# yard-ice-toplevel.net
KiCad netlist of a schematic drawn in Altium Designer
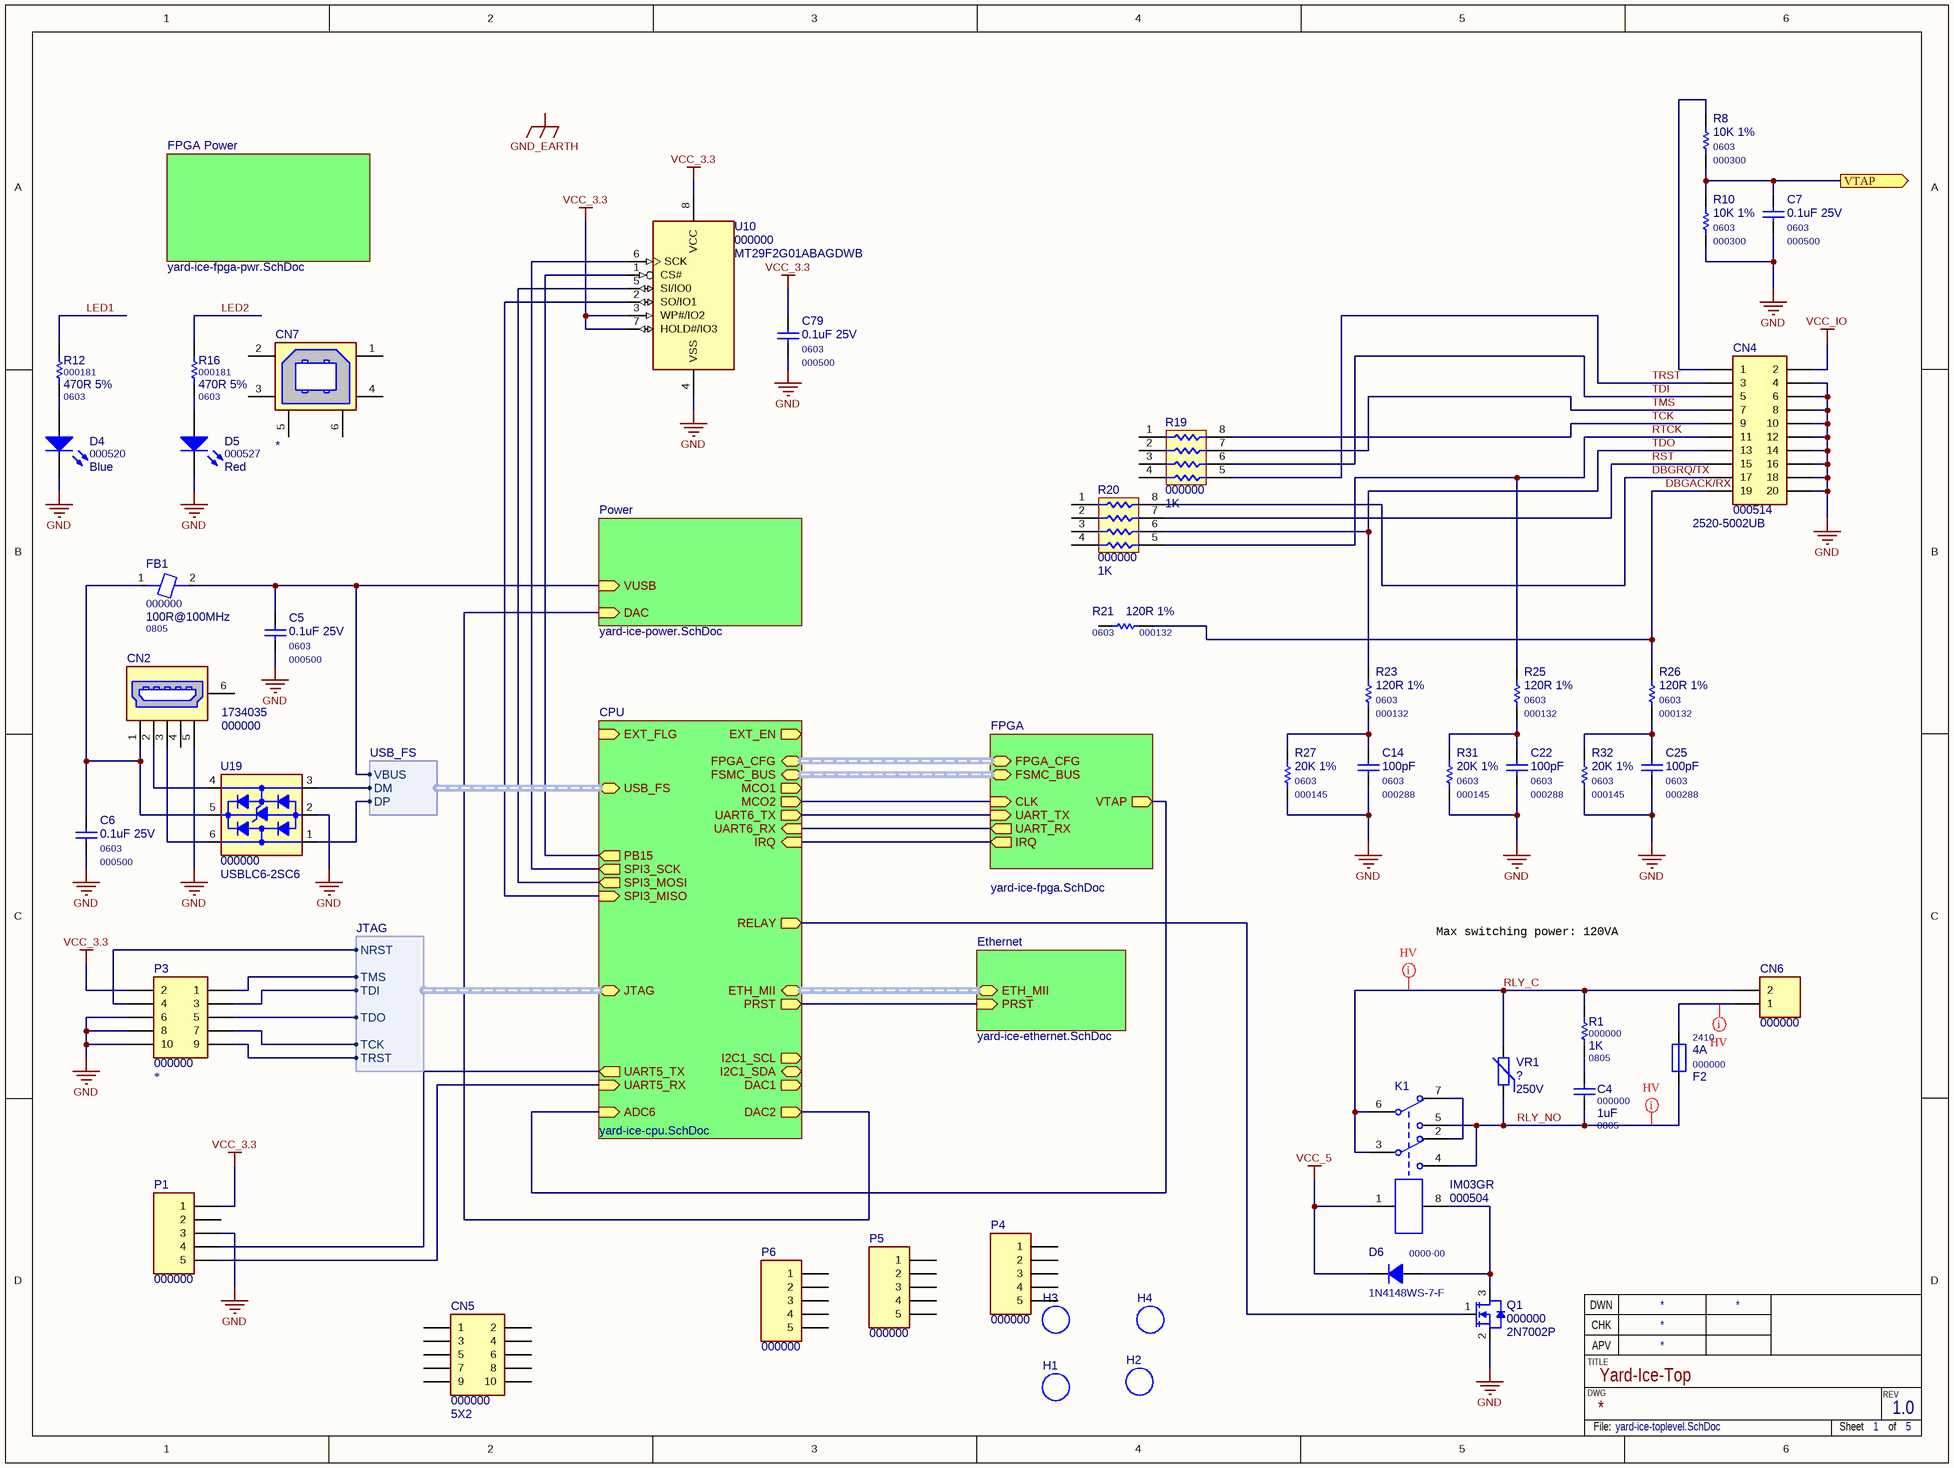
[diagram p0: yard-ice-toplevel.SchDoc]

(export (version "E")
  (design (tool "Eeschema 10.0.6"))
  (components
    (comp (ref "C4")
      (value "000000")
      (footprint "C0805HV")
      (description "SMD Ceramic Chip Capacitor - 0805")
      (fields (field (name "ALTIUM_VALUE") "1uF") (field (name "PACKAGE") "0805"))
      (libsource (lib "discrete-sm") (part "C0805"))
    )
    (comp (ref "C5")
      (value "000500")
      (footprint "C0603M")
      (description "SMD Ceramic Chip Capacitor - 0603 - X7R")
      (fields
        (field (name "ALTIUM_VALUE") "0.1uF 25V")
        (field (name "PACKAGE") "0603")
        (field (name "MF") "TDK")
      )
      (libsource (lib "discrete-sm") (part "C0603"))
    )
    (comp (ref "C6")
      (value "000500")
      (footprint "C0603M")
      (description "SMD Ceramic Chip Capacitor - 0603 - X7R")
      (fields
        (field (name "ALTIUM_VALUE") "0.1uF 25V")
        (field (name "PACKAGE") "0603")
        (field (name "MF") "TDK")
      )
      (libsource (lib "discrete-sm") (part "C0603"))
    )
    (comp (ref "C7")
      (value "000500")
      (footprint "C0603M")
      (description "SMD Ceramic Chip Capacitor - 0603 - X7R")
      (fields
        (field (name "ALTIUM_VALUE") "0.1uF 25V")
        (field (name "PACKAGE") "0603")
        (field (name "MF") "TDK")
      )
      (libsource (lib "discrete-sm") (part "C0603"))
    )
    (comp (ref "C14")
      (value "000288")
      (footprint "C0603M")
      (description "SMD Ceramic Chip Capacitor - 0603")
      (fields (field (name "ALTIUM_VALUE") "100pF") (field (name "PACKAGE") "0603"))
      (libsource (lib "discrete-sm") (part "C0603"))
    )
    (comp (ref "C22")
      (value "000288")
      (footprint "C0603M")
      (description "SMD Ceramic Chip Capacitor - 0603")
      (fields (field (name "ALTIUM_VALUE") "100pF") (field (name "PACKAGE") "0603"))
      (libsource (lib "discrete-sm") (part "C0603"))
    )
    (comp (ref "C25")
      (value "000288")
      (footprint "C0603M")
      (description "SMD Ceramic Chip Capacitor - 0603")
      (fields (field (name "ALTIUM_VALUE") "100pF") (field (name "PACKAGE") "0603"))
      (libsource (lib "discrete-sm") (part "C0603"))
    )
    (comp (ref "C79")
      (value "000500")
      (footprint "C0603M")
      (description "SMD Ceramic Chip Capacitor - 0603 - X7R")
      (fields
        (field (name "ALTIUM_VALUE") "0.1uF 25V")
        (field (name "PACKAGE") "0603")
        (field (name "MF") "TDK")
      )
      (libsource (lib "discrete-sm") (part "C0603"))
    )
    (comp (ref "CN2")
      (value "1734035")
      (footprint "1734035")
      (description "USB Type B Mini - Right Angle - SMD")
      (fields (field (name "MF") "Tyco") (field (name "PN") "000000") (field (name "Comment") "000000"))
      (libsource (lib "tyco-conn") (part "1734035"))
    )
    (comp (ref "CN4")
      (value "000514")
      (footprint "TST-110-04-G-D-RA")
      (description "Shrouded Header, 20 Pos, Right Angle")
      (fields (field (name "ALTIUM_VALUE") "2520-5002UB") (field (name "MF") "3M"))
      (libsource (lib "samtec-board-to-board") (part "Header 10X2"))
    )
    (comp (ref "CN5")
      (value "000000")
      (footprint "TST-105-04-G-D-RA")
      (description "Socket 5-Pin, Dual row")
      (fields (field (name "MF") "Samtec") (field (name "ALTIUM_VALUE") "5X2"))
      (libsource (lib "samtec-board-to-board") (part "Header 5X2"))
    )
    (comp (ref "CN6")
      (value "000000")
      (footprint "691322110002")
      (description "Terminal Block, Header, 2-Pos")
      (libsource (lib "wurth") (part "Term Blk 2"))
    )
    (comp (ref "CN7")
      (value "*")
      (footprint "4-1734376")
      (description "USB Type B - Right Angle - Thru Hole")
      (libsource (lib "tyco-conn") (part "4-1734376"))
    )
    (comp (ref "D4")
      (value "000520")
      (footprint "LED0805L LP")
      (description "LED SMD 0805")
      (fields (field (name "ALTIUM_VALUE") "Blue"))
      (libsource (lib "discrete-sm") (part "LED0805LP"))
    )
    (comp (ref "D5")
      (value "000527")
      (footprint "LED0805L LP")
      (description "LED SMD 0805")
      (fields (field (name "ALTIUM_VALUE") "Red"))
      (libsource (lib "discrete-sm") (part "LED0805LP"))
    )
    (comp (ref "D6")
      (value "0000-00")
      (footprint "SOD-323-M")
      (description "Fast Switching Diode 100V 150mA")
      (fields (field (name "MF") "Diodes Inc") (field (name "MF PN") "1N4148WS-7-F"))
      (libsource (lib "diodes-inc") (part "1N4148WS"))
    )
    (comp (ref "F2")
      (value "000000")
      (footprint "F2410")
      (fields (field (name "PACKAGE") "2410") (field (name "ALTIUM_VALUE") "4A"))
      (libsource (lib "discrete-sm") (part "F2410"))
    )
    (comp (ref "FB1")
      (value "000000")
      (footprint "L0805M")
      (description "SMD Chip Ferrite Bead - 0805")
      (fields (field (name "ALTIUM_VALUE") "100R@100MHz") (field (name "PACKAGE") "0805"))
      (libsource (lib "discrete-sm") (part "FB0805"))
    )
    (comp (ref "H1")
      (value "Hole Non Plated")
      (footprint "Hole NP 3.2x5.0x5.0")
      (libsource (lib "mechanical") (part "Hole Non Plated"))
    )
    (comp (ref "H2")
      (value "Hole Non Plated")
      (footprint "Hole NP 3.2x5.0x5.0")
      (libsource (lib "mechanical") (part "Hole Non Plated"))
    )
    (comp (ref "H3")
      (value "Hole Non Plated")
      (footprint "Hole NP 3.2x5.0x5.0")
      (libsource (lib "mechanical") (part "Hole Non Plated"))
    )
    (comp (ref "H4")
      (value "Hole Non Plated")
      (footprint "Hole NP 3.2x5.0x5.0")
      (libsource (lib "mechanical") (part "Hole Non Plated"))
    )
    (comp (ref "K1")
      (value "000504")
      (footprint "Relay-10X6")
      (description "Dual-Pole Dual-Throw Relay")
      (fields (field (name "ALTIUM_VALUE") "IM03GR") (field (name "MF") "Tyco"))
      (libsource (lib "sm-electromechanical") (part "Relay-DPDT"))
    )
    (comp (ref "P1")
      (value "000000")
      (footprint "TSW-105-07-G-S")
      (description "Header, 5-Pin")
      (libsource (lib "samtec-board-to-board") (part "Header 5"))
    )
    (comp (ref "P3")
      (value "000000")
      (footprint "TSW-105-07-G-D")
      (description "Socket 5-Pin, Dual row")
      (fields (field (name "ALTIUM_VALUE") "*"))
      (libsource (lib "samtec-std-hdr") (part "Header 5X2"))
    )
    (comp (ref "P4")
      (value "000000")
      (footprint "TSW-105-07-G-S")
      (description "Header, 5-Pin")
      (libsource (lib "samtec-board-to-board") (part "Header 5"))
    )
    (comp (ref "P5")
      (value "000000")
      (footprint "TSW-105-07-G-S")
      (description "Header, 5-Pin")
      (libsource (lib "samtec-board-to-board") (part "Header 5"))
    )
    (comp (ref "P6")
      (value "000000")
      (footprint "TSW-105-07-G-S")
      (description "Header, 5-Pin")
      (libsource (lib "samtec-board-to-board") (part "Header 5"))
    )
    (comp (ref "Q1")
      (value "000000")
      (footprint "SOT-23-M")
      (description "N-Channel MOSFET 60V 360mA SOT-23")
      (fields (field (name "ALTIUM_VALUE") "2N7002P"))
      (libsource (lib "nxp") (part "2N7002P"))
    )
    (comp (ref "R1")
      (value "000000")
      (footprint "R0805HV")
      (description "SMD Chip Resistor - 0805")
      (fields (field (name "ALTIUM_VALUE") "1K") (field (name "PACKAGE") "0805"))
      (libsource (lib "discrete-sm") (part "R0805"))
    )
    (comp (ref "R8")
      (value "000300")
      (footprint "R0603M")
      (description "SMD Chip Resistor - 0603")
      (fields (field (name "ALTIUM_VALUE") "10K 1%") (field (name "PACKAGE") "0603"))
      (libsource (lib "discrete-sm") (part "R0603"))
    )
    (comp (ref "R10")
      (value "000300")
      (footprint "R0603M")
      (description "SMD Chip Resistor - 0603")
      (fields (field (name "ALTIUM_VALUE") "10K 1%") (field (name "PACKAGE") "0603"))
      (libsource (lib "discrete-sm") (part "R0603"))
    )
    (comp (ref "R12")
      (value "000181")
      (footprint "R0603M")
      (description "SMD Chip Resistor - 0603")
      (fields (field (name "ALTIUM_VALUE") "470R 5%") (field (name "PACKAGE") "0603"))
      (libsource (lib "discrete-sm") (part "R0603"))
    )
    (comp (ref "R16")
      (value "000181")
      (footprint "R0603M")
      (description "SMD Chip Resistor - 0603")
      (fields (field (name "ALTIUM_VALUE") "470R 5%") (field (name "PACKAGE") "0603"))
      (libsource (lib "discrete-sm") (part "R0603"))
    )
    (comp (ref "R19")
      (value "000000")
      (footprint "R0603x4L")
      (description "SMD Chip Resistor Array - 4x0603")
      (fields (field (name "ALTIUM_VALUE") "1K"))
      (libsource (lib "discrete-sm") (part "R0603x4"))
    )
    (comp (ref "R20")
      (value "000000")
      (footprint "R0603x4L")
      (description "SMD Chip Resistor Array - 4x0603")
      (fields (field (name "ALTIUM_VALUE") "1K"))
      (libsource (lib "discrete-sm") (part "R0603x4"))
    )
    (comp (ref "R21")
      (value "000132")
      (footprint "R0603M")
      (description "SMD Chip Resistor - 0603")
      (fields (field (name "ALTIUM_VALUE") "120R 1%") (field (name "PACKAGE") "0603"))
      (libsource (lib "discrete-sm") (part "R0603"))
    )
    (comp (ref "R23")
      (value "000132")
      (footprint "R0603M")
      (description "SMD Chip Resistor - 0603")
      (fields (field (name "ALTIUM_VALUE") "120R 1%") (field (name "PACKAGE") "0603"))
      (libsource (lib "discrete-sm") (part "R0603"))
    )
    (comp (ref "R25")
      (value "000132")
      (footprint "R0603M")
      (description "SMD Chip Resistor - 0603")
      (fields (field (name "ALTIUM_VALUE") "120R 1%") (field (name "PACKAGE") "0603"))
      (libsource (lib "discrete-sm") (part "R0603"))
    )
    (comp (ref "R26")
      (value "000132")
      (footprint "R0603M")
      (description "SMD Chip Resistor - 0603")
      (fields (field (name "ALTIUM_VALUE") "120R 1%") (field (name "PACKAGE") "0603"))
      (libsource (lib "discrete-sm") (part "R0603"))
    )
    (comp (ref "R27")
      (value "000145")
      (footprint "R0603M")
      (description "SMD Chip Resistor - 0603")
      (fields (field (name "ALTIUM_VALUE") "20K 1%") (field (name "PACKAGE") "0603"))
      (libsource (lib "discrete-sm") (part "R0603"))
    )
    (comp (ref "R31")
      (value "000145")
      (footprint "R0603M")
      (description "SMD Chip Resistor - 0603")
      (fields (field (name "ALTIUM_VALUE") "20K 1%") (field (name "PACKAGE") "0603"))
      (libsource (lib "discrete-sm") (part "R0603"))
    )
    (comp (ref "R32")
      (value "000145")
      (footprint "R0603M")
      (description "SMD Chip Resistor - 0603")
      (fields (field (name "ALTIUM_VALUE") "20K 1%") (field (name "PACKAGE") "0603"))
      (libsource (lib "discrete-sm") (part "R0603"))
    )
    (comp (ref "U10")
      (value "000000")
      (footprint "U-PDFN-8")
      (description "2Gb NANDl Flash Memory,  133MHz, SPI")
      (fields (field (name "MF") "Micron") (field (name "ALTIUM_VALUE") "MT29F2G01ABAGDWB"))
      (libsource (lib "micron") (part "MT29F2G01ABAGDWB"))
    )
    (comp (ref "U19")
      (value "000000")
      (footprint "SOT23-6L")
      (description "USB ESD Protection")
      (fields (field (name "MF") "STMicroelectronics") (field (name "ALTIUM_VALUE") "USBLC6-2SC6"))
      (libsource (lib "st") (part "USBLC6-2SC6"))
    )
    (comp (ref "VR1")
      (value "?")
      (footprint "MOV7x4.8-5.0")
      (description "Varistor (Voltage-Sensitive Resistor)")
      (fields (field (name "ALTIUM_VALUE") "250V"))
      (libsource (lib "discrete-pth") (part "Varistor"))
    )
  )
  (nets
    (net (code "5") (name "/DBGACK{slash}RX") (class "Default")
      (node (ref "CN4") (pin "19") (pinfunction "19_19") (pintype "passive"))
      (node (ref "R21") (pin "1") (pinfunction "1_1") (pintype "passive"))
      (node (ref "R26") (pin "1") (pinfunction "1_1") (pintype "passive"))
    )
    (net (code "6") (name "/DBGRQ{slash}TX") (class "Default")
      (node (ref "CN4") (pin "17") (pinfunction "17_17") (pintype "passive"))
      (node (ref "R20") (pin "8") (pinfunction "8_8") (pintype "passive"))
    )
    (net (code "15") (name "/LED1") (class "Default")
      (node (ref "R12") (pin "1") (pinfunction "1_1") (pintype "passive"))
    )
    (net (code "16") (name "/LED2") (class "Default")
      (node (ref "R16") (pin "1") (pinfunction "1_1") (pintype "passive"))
    )
    (net (code "19") (name "/PB15") (class "Default")
      (node (ref "U10") (pin "1") (pinfunction "CS#_1") (pintype "input"))
    )
    (net (code "21") (name "/RELAY") (class "Default")
      (node (ref "Q1") (pin "1") (pinfunction "G_1") (pintype "passive"))
    )
    (net (code "22") (name "/RLY_C") (class "Default")
      (node (ref "CN6") (pin "2") (pinfunction "2_2") (pintype "passive"))
      (node (ref "K1") (pin "3") (pinfunction "3_3") (pintype "passive"))
      (node (ref "K1") (pin "6") (pinfunction "6_6") (pintype "passive"))
      (node (ref "R1") (pin "2") (pinfunction "2_2") (pintype "passive"))
      (node (ref "VR1") (pin "2") (pinfunction "2_2") (pintype "passive"))
    )
    (net (code "23") (name "/RLY_NO") (class "Default")
      (node (ref "C4") (pin "2") (pinfunction "2_2") (pintype "passive"))
      (node (ref "F2") (pin "1") (pinfunction "1_1") (pintype "passive"))
      (node (ref "K1") (pin "4") (pinfunction "4_4") (pintype "passive"))
      (node (ref "K1") (pin "5") (pinfunction "5_5") (pintype "passive"))
      (node (ref "VR1") (pin "1") (pinfunction "1_1") (pintype "passive"))
    )
    (net (code "24") (name "/RST") (class "Default")
      (node (ref "CN4") (pin "15") (pinfunction "15_15") (pintype "passive"))
      (node (ref "R20") (pin "7") (pinfunction "7_7") (pintype "passive"))
    )
    (net (code "25") (name "/RTCK") (class "Default")
      (node (ref "CN4") (pin "11") (pinfunction "11_11") (pintype "passive"))
      (node (ref "R20") (pin "5") (pinfunction "5_5") (pintype "passive"))
      (node (ref "R25") (pin "1") (pinfunction "1_1") (pintype "passive"))
    )
    (net (code "26") (name "/SPI3_MISO") (class "Default")
      (node (ref "U10") (pin "2") (pinfunction "SO/IO1_2") (pintype "bidirectional"))
    )
    (net (code "27") (name "/SPI3_MOSI") (class "Default")
      (node (ref "U10") (pin "5") (pinfunction "SI/IO0_5") (pintype "bidirectional"))
    )
    (net (code "28") (name "/SPI3_SCK") (class "Default")
      (node (ref "U10") (pin "6") (pinfunction "SCK_6") (pintype "input"))
    )
    (net (code "29") (name "/TCK") (class "Default")
      (node (ref "CN4") (pin "9") (pinfunction "9_9") (pintype "passive"))
      (node (ref "R19") (pin "8") (pinfunction "8_8") (pintype "passive"))
    )
    (net (code "30") (name "/TDI") (class "Default")
      (node (ref "CN4") (pin "5") (pinfunction "5_5") (pintype "passive"))
      (node (ref "R19") (pin "6") (pinfunction "6_6") (pintype "passive"))
    )
    (net (code "31") (name "/TDO") (class "Default")
      (node (ref "CN4") (pin "13") (pinfunction "13_13") (pintype "passive"))
      (node (ref "R20") (pin "6") (pinfunction "6_6") (pintype "passive"))
      (node (ref "R23") (pin "1") (pinfunction "1_1") (pintype "passive"))
    )
    (net (code "32") (name "/TMS") (class "Default")
      (node (ref "CN4") (pin "7") (pinfunction "7_7") (pintype "passive"))
      (node (ref "R19") (pin "7") (pinfunction "7_7") (pintype "passive"))
    )
    (net (code "33") (name "/TRST") (class "Default")
      (node (ref "CN4") (pin "3") (pinfunction "3_3") (pintype "passive"))
      (node (ref "R19") (pin "5") (pinfunction "5_5") (pintype "passive"))
    )
    (net (code "34") (name "/UART5_RX") (class "Default")
      (node (ref "P1") (pin "5") (pinfunction "5_5") (pintype "passive"))
    )
    (net (code "35") (name "/UART5_TX") (class "Default")
      (node (ref "P1") (pin "4") (pinfunction "4_4") (pintype "passive"))
    )
    (net (code "38") (name "/VTAP") (class "Default")
      (node (ref "C7") (pin "1") (pinfunction "1_1") (pintype "passive"))
      (node (ref "R10") (pin "1") (pinfunction "1_1") (pintype "passive"))
      (node (ref "R8") (pin "2") (pinfunction "2_2") (pintype "passive"))
    )
    (net (code "40") (name "/VUSB") (class "Default")
      (node (ref "C5") (pin "1") (pinfunction "1_1") (pintype "passive"))
      (node (ref "FB1") (pin "2") (pinfunction "2_2") (pintype "passive"))
    )
    (net (code "43") (name "GND") (class "Default")
      (node (ref "C14") (pin "2") (pinfunction "2_2") (pintype "passive"))
      (node (ref "C22") (pin "2") (pinfunction "2_2") (pintype "passive"))
      (node (ref "C25") (pin "2") (pinfunction "2_2") (pintype "passive"))
      (node (ref "C5") (pin "2") (pinfunction "2_2") (pintype "passive"))
      (node (ref "C6") (pin "2") (pinfunction "2_2") (pintype "passive"))
      (node (ref "C7") (pin "2") (pinfunction "2_2") (pintype "passive"))
      (node (ref "C79") (pin "2") (pinfunction "2_2") (pintype "passive"))
      (node (ref "CN2") (pin "5") (pinfunction "SHIELD_5") (pintype "passive"))
      (node (ref "CN4") (pin "10") (pinfunction "10_10") (pintype "passive"))
      (node (ref "CN4") (pin "12") (pinfunction "12_12") (pintype "passive"))
      (node (ref "CN4") (pin "14") (pinfunction "14_14") (pintype "passive"))
      (node (ref "CN4") (pin "16") (pinfunction "16_16") (pintype "passive"))
      (node (ref "CN4") (pin "18") (pinfunction "18_18") (pintype "passive"))
      (node (ref "CN4") (pin "20") (pinfunction "20_20") (pintype "passive"))
      (node (ref "CN4") (pin "4") (pinfunction "4_4") (pintype "passive"))
      (node (ref "CN4") (pin "6") (pinfunction "6_6") (pintype "passive"))
      (node (ref "CN4") (pin "8") (pinfunction "8_8") (pintype "passive"))
      (node (ref "D4") (pin "2") (pinfunction "K_2") (pintype "passive"))
      (node (ref "D5") (pin "2") (pinfunction "K_2") (pintype "passive"))
      (node (ref "P1") (pin "3") (pinfunction "3_3") (pintype "passive"))
      (node (ref "P3") (pin "10") (pinfunction "10_10") (pintype "passive"))
      (node (ref "P3") (pin "6") (pinfunction "6_6") (pintype "passive"))
      (node (ref "P3") (pin "8") (pinfunction "8_8") (pintype "passive"))
      (node (ref "Q1") (pin "2") (pinfunction "S_2") (pintype "passive"))
      (node (ref "R10") (pin "2") (pinfunction "2_2") (pintype "passive"))
      (node (ref "R27") (pin "2") (pinfunction "2_2") (pintype "passive"))
      (node (ref "R31") (pin "2") (pinfunction "2_2") (pintype "passive"))
      (node (ref "R32") (pin "2") (pinfunction "2_2") (pintype "passive"))
      (node (ref "U10") (pin "4") (pinfunction "VSS_4") (pintype "power_in"))
      (node (ref "U19") (pin "2") (pinfunction "GND_2") (pintype "power_in"))
    )
    (net (code "45") (name "Net-(C4-Pad1)") (class "Default")
      (node (ref "C4") (pin "1") (pinfunction "1_1") (pintype "passive"))
      (node (ref "R1") (pin "1") (pinfunction "1_1") (pintype "passive"))
    )
    (net (code "46") (name "Net-(C14-Pad1)") (class "Default")
      (node (ref "C14") (pin "1") (pinfunction "1_1") (pintype "passive"))
      (node (ref "R23") (pin "2") (pinfunction "2_2") (pintype "passive"))
      (node (ref "R27") (pin "1") (pinfunction "1_1") (pintype "passive"))
    )
    (net (code "47") (name "Net-(C22-Pad1)") (class "Default")
      (node (ref "C22") (pin "1") (pinfunction "1_1") (pintype "passive"))
      (node (ref "R25") (pin "2") (pinfunction "2_2") (pintype "passive"))
      (node (ref "R31") (pin "1") (pinfunction "1_1") (pintype "passive"))
    )
    (net (code "48") (name "Net-(C25-Pad1)") (class "Default")
      (node (ref "C25") (pin "1") (pinfunction "1_1") (pintype "passive"))
      (node (ref "R26") (pin "2") (pinfunction "2_2") (pintype "passive"))
      (node (ref "R32") (pin "1") (pinfunction "1_1") (pintype "passive"))
    )
    (net (code "49") (name "Net-(CN4-Pad1)") (class "Default")
      (node (ref "CN4") (pin "1") (pinfunction "1_1") (pintype "passive"))
      (node (ref "R8") (pin "1") (pinfunction "1_1") (pintype "passive"))
    )
    (net (code "50") (name "Net-(CN6-Pad1)") (class "Default")
      (node (ref "CN6") (pin "1") (pinfunction "1_1") (pintype "passive"))
      (node (ref "F2") (pin "2") (pinfunction "2_2") (pintype "passive"))
    )
    (net (code "51") (name "Net-(D4-A)") (class "Default")
      (node (ref "D4") (pin "1") (pinfunction "A_1") (pintype "passive"))
      (node (ref "R12") (pin "2") (pinfunction "2_2") (pintype "passive"))
    )
    (net (code "52") (name "Net-(D5-A)") (class "Default")
      (node (ref "D5") (pin "1") (pinfunction "A_1") (pintype "passive"))
      (node (ref "R16") (pin "2") (pinfunction "2_2") (pintype "passive"))
    )
    (net (code "53") (name "Net-(D6-A)") (class "Default")
      (node (ref "D6") (pin "1") (pinfunction "A_1") (pintype "passive"))
      (node (ref "K1") (pin "8") (pinfunction "8_8") (pintype "passive"))
      (node (ref "Q1") (pin "3") (pinfunction "D_3") (pintype "passive"))
    )
    (net (code "54") (name "Net-(K1-Pad2)") (class "Default")
      (node (ref "K1") (pin "2") (pinfunction "2_2") (pintype "passive"))
      (node (ref "K1") (pin "7") (pinfunction "7_7") (pintype "passive"))
    )
    (net (code "55") (name "Net-(U19-I{slash}O1)") (class "Default")
      (node (ref "CN2") (pin "3") (pinfunction "3_3") (pintype "passive"))
      (node (ref "U19") (pin "6") (pinfunction "I/O1_6") (pintype "open_collector"))
    )
    (net (code "56") (name "Net-(U19-I{slash}O2)") (class "Default")
      (node (ref "CN2") (pin "2") (pinfunction "2_2") (pintype "passive"))
      (node (ref "U19") (pin "4") (pinfunction "I/O2_4") (pintype "open_collector"))
    )
    (net (code "57") (name "Net-(U19-VBUS)") (class "Default")
      (node (ref "C6") (pin "1") (pinfunction "1_1") (pintype "passive"))
      (node (ref "CN2") (pin "1") (pinfunction "1_1") (pintype "passive"))
      (node (ref "FB1") (pin "1") (pinfunction "1_1") (pintype "passive"))
      (node (ref "U19") (pin "5") (pinfunction "VBUS_5") (pintype "power_in"))
    )
    (net (code "58") (name "VCC_3.3") (class "Default")
      (node (ref "C79") (pin "1") (pinfunction "1_1") (pintype "passive"))
      (node (ref "P1") (pin "1") (pinfunction "1_1") (pintype "passive"))
      (node (ref "P3") (pin "2") (pinfunction "2_2") (pintype "passive"))
      (node (ref "U10") (pin "3") (pinfunction "WP#/IO2_3") (pintype "input"))
      (node (ref "U10") (pin "7") (pinfunction "HOLD#/IO3_7") (pintype "bidirectional"))
      (node (ref "U10") (pin "8") (pinfunction "VCC_8") (pintype "power_in"))
    )
    (net (code "59") (name "VCC_5") (class "Default")
      (node (ref "D6") (pin "2") (pinfunction "K_2") (pintype "passive"))
      (node (ref "K1") (pin "1") (pinfunction "1_1") (pintype "passive"))
    )
    (net (code "60") (name "VCC_IO") (class "Default")
      (node (ref "CN4") (pin "2") (pinfunction "2_2") (pintype "passive"))
    )
    (net (code "61") (name "unconnected-(CN2-Pad4)") (class "Default")
      (node (ref "CN2") (pin "4") (pinfunction "4_4") (pintype "passive"))
    )
    (net (code "62") (name "unconnected-(CN2-SHIELD-Pad6)") (class "Default")
      (node (ref "CN2") (pin "6") (pinfunction "SHIELD_6") (pintype "passive"))
    )
    (net (code "63") (name "unconnected-(CN5-Pad1)") (class "Default")
      (node (ref "CN5") (pin "1") (pinfunction "1_1") (pintype "passive"))
    )
    (net (code "64") (name "unconnected-(CN5-Pad2)") (class "Default")
      (node (ref "CN5") (pin "2") (pinfunction "2_2") (pintype "passive"))
    )
    (net (code "65") (name "unconnected-(CN5-Pad3)") (class "Default")
      (node (ref "CN5") (pin "3") (pinfunction "3_3") (pintype "passive"))
    )
    (net (code "66") (name "unconnected-(CN5-Pad4)") (class "Default")
      (node (ref "CN5") (pin "4") (pinfunction "4_4") (pintype "passive"))
    )
    (net (code "67") (name "unconnected-(CN5-Pad5)") (class "Default")
      (node (ref "CN5") (pin "5") (pinfunction "5_5") (pintype "passive"))
    )
    (net (code "68") (name "unconnected-(CN5-Pad6)") (class "Default")
      (node (ref "CN5") (pin "6") (pinfunction "6_6") (pintype "passive"))
    )
    (net (code "69") (name "unconnected-(CN5-Pad7)") (class "Default")
      (node (ref "CN5") (pin "7") (pinfunction "7_7") (pintype "passive"))
    )
    (net (code "70") (name "unconnected-(CN5-Pad8)") (class "Default")
      (node (ref "CN5") (pin "8") (pinfunction "8_8") (pintype "passive"))
    )
    (net (code "71") (name "unconnected-(CN5-Pad9)") (class "Default")
      (node (ref "CN5") (pin "9") (pinfunction "9_9") (pintype "passive"))
    )
    (net (code "72") (name "unconnected-(CN5-Pad10)") (class "Default")
      (node (ref "CN5") (pin "10") (pinfunction "10_10") (pintype "passive"))
    )
    (net (code "73") (name "unconnected-(CN7-Pad1)") (class "Default")
      (node (ref "CN7") (pin "1") (pinfunction "1_1") (pintype "passive"))
    )
    (net (code "74") (name "unconnected-(CN7-Pad2)") (class "Default")
      (node (ref "CN7") (pin "2") (pinfunction "2_2") (pintype "passive"))
    )
    (net (code "75") (name "unconnected-(CN7-Pad3)") (class "Default")
      (node (ref "CN7") (pin "3") (pinfunction "3_3") (pintype "passive"))
    )
    (net (code "76") (name "unconnected-(CN7-Pad4)") (class "Default")
      (node (ref "CN7") (pin "4") (pinfunction "4_4") (pintype "passive"))
    )
    (net (code "77") (name "unconnected-(CN7-SHIELD-Pad5)") (class "Default")
      (node (ref "CN7") (pin "5") (pinfunction "SHIELD_5") (pintype "passive"))
    )
    (net (code "78") (name "unconnected-(CN7-SHIELD-Pad6)") (class "Default")
      (node (ref "CN7") (pin "6") (pinfunction "SHIELD_6") (pintype "passive"))
    )
    (net (code "79") (name "unconnected-(P1-Pad2)") (class "Default")
      (node (ref "P1") (pin "2") (pinfunction "2_2") (pintype "passive"))
    )
    (net (code "80") (name "unconnected-(P3-Pad1)") (class "Default")
      (node (ref "P3") (pin "1") (pinfunction "1_1") (pintype "passive"))
    )
    (net (code "81") (name "unconnected-(P3-Pad3)") (class "Default")
      (node (ref "P3") (pin "3") (pinfunction "3_3") (pintype "passive"))
    )
    (net (code "82") (name "unconnected-(P3-Pad4)") (class "Default")
      (node (ref "P3") (pin "4") (pinfunction "4_4") (pintype "passive"))
    )
    (net (code "83") (name "unconnected-(P3-Pad5)") (class "Default")
      (node (ref "P3") (pin "5") (pinfunction "5_5") (pintype "passive"))
    )
    (net (code "84") (name "unconnected-(P3-Pad7)") (class "Default")
      (node (ref "P3") (pin "7") (pinfunction "7_7") (pintype "passive"))
    )
    (net (code "85") (name "unconnected-(P3-Pad9)") (class "Default")
      (node (ref "P3") (pin "9") (pinfunction "9_9") (pintype "passive"))
    )
    (net (code "86") (name "unconnected-(P4-Pad1)") (class "Default")
      (node (ref "P4") (pin "1") (pinfunction "1_1") (pintype "passive"))
    )
    (net (code "87") (name "unconnected-(P4-Pad2)") (class "Default")
      (node (ref "P4") (pin "2") (pinfunction "2_2") (pintype "passive"))
    )
    (net (code "88") (name "unconnected-(P4-Pad3)") (class "Default")
      (node (ref "P4") (pin "3") (pinfunction "3_3") (pintype "passive"))
    )
    (net (code "89") (name "unconnected-(P4-Pad4)") (class "Default")
      (node (ref "P4") (pin "4") (pinfunction "4_4") (pintype "passive"))
    )
    (net (code "90") (name "unconnected-(P4-Pad5)") (class "Default")
      (node (ref "P4") (pin "5") (pinfunction "5_5") (pintype "passive"))
    )
    (net (code "91") (name "unconnected-(P5-Pad1)") (class "Default")
      (node (ref "P5") (pin "1") (pinfunction "1_1") (pintype "passive"))
    )
    (net (code "92") (name "unconnected-(P5-Pad2)") (class "Default")
      (node (ref "P5") (pin "2") (pinfunction "2_2") (pintype "passive"))
    )
    (net (code "93") (name "unconnected-(P5-Pad3)") (class "Default")
      (node (ref "P5") (pin "3") (pinfunction "3_3") (pintype "passive"))
    )
    (net (code "94") (name "unconnected-(P5-Pad4)") (class "Default")
      (node (ref "P5") (pin "4") (pinfunction "4_4") (pintype "passive"))
    )
    (net (code "95") (name "unconnected-(P5-Pad5)") (class "Default")
      (node (ref "P5") (pin "5") (pinfunction "5_5") (pintype "passive"))
    )
    (net (code "96") (name "unconnected-(P6-Pad1)") (class "Default")
      (node (ref "P6") (pin "1") (pinfunction "1_1") (pintype "passive"))
    )
    (net (code "97") (name "unconnected-(P6-Pad2)") (class "Default")
      (node (ref "P6") (pin "2") (pinfunction "2_2") (pintype "passive"))
    )
    (net (code "98") (name "unconnected-(P6-Pad3)") (class "Default")
      (node (ref "P6") (pin "3") (pinfunction "3_3") (pintype "passive"))
    )
    (net (code "99") (name "unconnected-(P6-Pad4)") (class "Default")
      (node (ref "P6") (pin "4") (pinfunction "4_4") (pintype "passive"))
    )
    (net (code "100") (name "unconnected-(P6-Pad5)") (class "Default")
      (node (ref "P6") (pin "5") (pinfunction "5_5") (pintype "passive"))
    )
    (net (code "101") (name "unconnected-(R19-Pad1)") (class "Default")
      (node (ref "R19") (pin "1") (pinfunction "1_1") (pintype "passive"))
    )
    (net (code "102") (name "unconnected-(R19-Pad2)") (class "Default")
      (node (ref "R19") (pin "2") (pinfunction "2_2") (pintype "passive"))
    )
    (net (code "103") (name "unconnected-(R19-Pad3)") (class "Default")
      (node (ref "R19") (pin "3") (pinfunction "3_3") (pintype "passive"))
    )
    (net (code "104") (name "unconnected-(R19-Pad4)") (class "Default")
      (node (ref "R19") (pin "4") (pinfunction "4_4") (pintype "passive"))
    )
    (net (code "105") (name "unconnected-(R20-Pad1)") (class "Default")
      (node (ref "R20") (pin "1") (pinfunction "1_1") (pintype "passive"))
    )
    (net (code "106") (name "unconnected-(R20-Pad2)") (class "Default")
      (node (ref "R20") (pin "2") (pinfunction "2_2") (pintype "passive"))
    )
    (net (code "107") (name "unconnected-(R20-Pad3)") (class "Default")
      (node (ref "R20") (pin "3") (pinfunction "3_3") (pintype "passive"))
    )
    (net (code "108") (name "unconnected-(R20-Pad4)") (class "Default")
      (node (ref "R20") (pin "4") (pinfunction "4_4") (pintype "passive"))
    )
    (net (code "109") (name "unconnected-(R21-Pad2)") (class "Default")
      (node (ref "R21") (pin "2") (pinfunction "2_2") (pintype "passive"))
    )
    (net (code "110") (name "unconnected-(U19-IO{slash}1-Pad1)") (class "Default")
      (node (ref "U19") (pin "1") (pinfunction "IO/1_1") (pintype "power_in"))
    )
    (net (code "111") (name "unconnected-(U19-IO{slash}2-Pad3)") (class "Default")
      (node (ref "U19") (pin "3") (pinfunction "IO/2_3") (pintype "power_in"))
    )
  )
)
